# eurofima.net
KiCad netlist of a schematic drawn in EAGLE
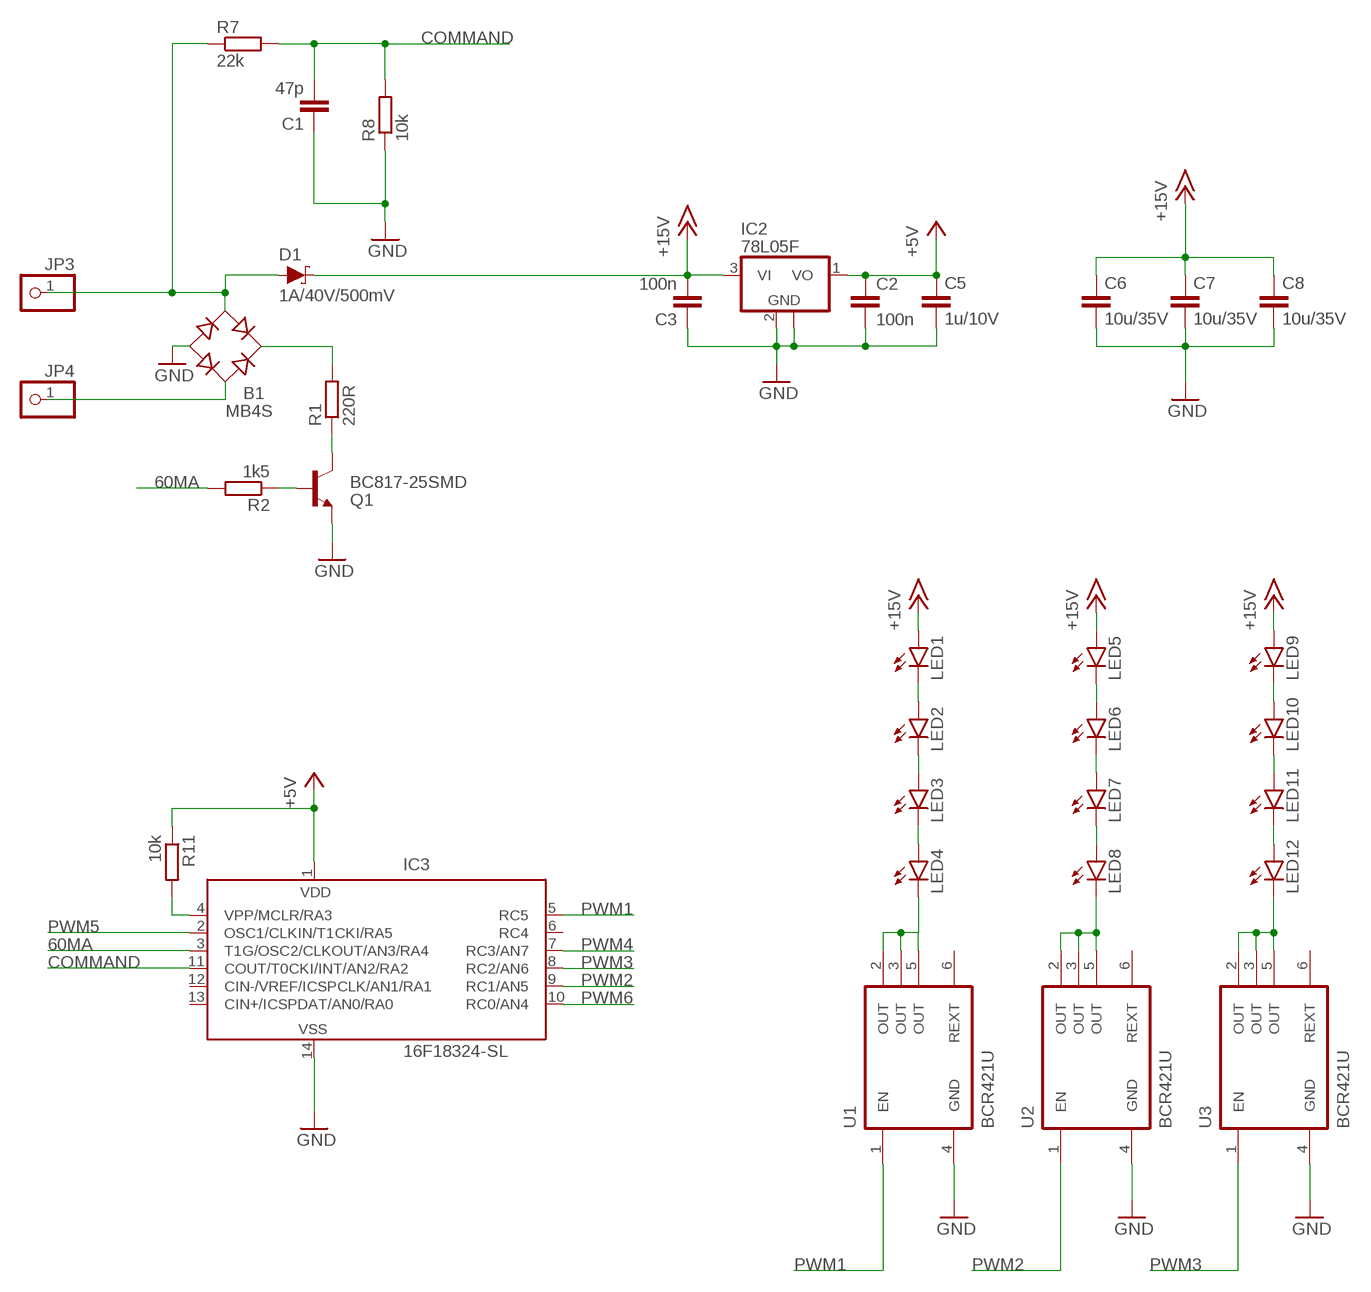
[diagram p0: schematic, sheet 1]

(export (version "E")
  (design (tool "Eeschema 10.0.6"))
  (components
    (comp (ref "B1")
      (value "MB4S")
      (footprint "eagle-import:SOIC-4")
      (libsource (lib "eagle-import") (part "MBS4"))
    )
    (comp (ref "C1")
      (value "47p")
      (footprint "eagle-import:C0805")
      (libsource (lib "eagle-import") (part "C-EUC0805"))
    )
    (comp (ref "C2")
      (value "100n")
      (footprint "eagle-import:C3216")
      (libsource (lib "eagle-import") (part "C-EUC3216"))
    )
    (comp (ref "C3")
      (value "100n")
      (footprint "eagle-import:C3216")
      (libsource (lib "eagle-import") (part "C-EUC3216"))
    )
    (comp (ref "C5")
      (value "1u/10V")
      (footprint "eagle-import:C3216")
      (libsource (lib "eagle-import") (part "C-EUC3216"))
    )
    (comp (ref "C6")
      (value "10u/35V")
      (footprint "eagle-import:C3216")
      (libsource (lib "eagle-import") (part "C-EUC3216"))
    )
    (comp (ref "C7")
      (value "10u/35V")
      (footprint "eagle-import:C3216")
      (libsource (lib "eagle-import") (part "C-EUC3216"))
    )
    (comp (ref "C8")
      (value "10u/35V")
      (footprint "eagle-import:C3216")
      (libsource (lib "eagle-import") (part "C-EUC3216"))
    )
    (comp (ref "D1")
      (value "1A/40V/500mV")
      (footprint "eagle-import:SMA-DIODE")
      (libsource (lib "eagle-import") (part "DIODE-SCHOTTKY-SS14"))
    )
    (comp (ref "IC2")
      (value "78L05F")
      (footprint "eagle-import:SOT89")
      (libsource (lib "eagle-import") (part "78LF05"))
    )
    (comp (ref "IC3")
      (value "16F18324-SL")
      (footprint "eagle-import:SO-14")
      (fields (field (name "MF") "MICROCHIP") (field (name "MPN") "PIC16F676-I/SL"))
      (libsource (lib "eagle-import") (part "PIC16F676SL"))
    )
    (comp (ref "JP3")
      (value "PINHD-1X1")
      (footprint "eagle-import:1X01")
      (libsource (lib "eagle-import") (part "PINHD-1X1"))
    )
    (comp (ref "JP4")
      (value "PINHD-1X1")
      (footprint "eagle-import:1X01")
      (libsource (lib "eagle-import") (part "PINHD-1X1"))
    )
    (comp (ref "LED1")
      (value "LEDKA-3528ASYC")
      (footprint "eagle-import:KA-3528ASYC")
      (libsource (lib "eagle-import") (part "LEDKA-3528ASYC"))
    )
    (comp (ref "LED2")
      (value "LEDKA-3528ASYC")
      (footprint "eagle-import:KA-3528ASYC")
      (libsource (lib "eagle-import") (part "LEDKA-3528ASYC"))
    )
    (comp (ref "LED3")
      (value "LEDKA-3528ASYC")
      (footprint "eagle-import:KA-3528ASYC")
      (libsource (lib "eagle-import") (part "LEDKA-3528ASYC"))
    )
    (comp (ref "LED4")
      (value "LEDKA-3528ASYC")
      (footprint "eagle-import:KA-3528ASYC")
      (libsource (lib "eagle-import") (part "LEDKA-3528ASYC"))
    )
    (comp (ref "LED5")
      (value "LEDKA-3528ASYC")
      (footprint "eagle-import:KA-3528ASYC")
      (libsource (lib "eagle-import") (part "LEDKA-3528ASYC"))
    )
    (comp (ref "LED6")
      (value "LEDKA-3528ASYC")
      (footprint "eagle-import:KA-3528ASYC")
      (libsource (lib "eagle-import") (part "LEDKA-3528ASYC"))
    )
    (comp (ref "LED7")
      (value "LEDKA-3528ASYC")
      (footprint "eagle-import:KA-3528ASYC")
      (libsource (lib "eagle-import") (part "LEDKA-3528ASYC"))
    )
    (comp (ref "LED8")
      (value "LEDKA-3528ASYC")
      (footprint "eagle-import:KA-3528ASYC")
      (libsource (lib "eagle-import") (part "LEDKA-3528ASYC"))
    )
    (comp (ref "LED9")
      (value "LEDKA-3528ASYC")
      (footprint "eagle-import:KA-3528ASYC")
      (libsource (lib "eagle-import") (part "LEDKA-3528ASYC"))
    )
    (comp (ref "LED10")
      (value "LEDKA-3528ASYC")
      (footprint "eagle-import:KA-3528ASYC")
      (libsource (lib "eagle-import") (part "LEDKA-3528ASYC"))
    )
    (comp (ref "LED11")
      (value "LEDKA-3528ASYC")
      (footprint "eagle-import:KA-3528ASYC")
      (libsource (lib "eagle-import") (part "LEDKA-3528ASYC"))
    )
    (comp (ref "LED12")
      (value "LEDKA-3528ASYC")
      (footprint "eagle-import:KA-3528ASYC")
      (libsource (lib "eagle-import") (part "LEDKA-3528ASYC"))
    )
    (comp (ref "Q1")
      (value "BC817-25SMD")
      (footprint "eagle-import:SOT23-BEC")
      (libsource (lib "eagle-import") (part "BC817SMD-25"))
    )
    (comp (ref "R1")
      (value "220R")
      (footprint "eagle-import:R1206")
      (libsource (lib "eagle-import") (part "R-EU_R1206"))
    )
    (comp (ref "R2")
      (value "1k5")
      (footprint "eagle-import:R1206")
      (libsource (lib "eagle-import") (part "R-EU_R1206"))
    )
    (comp (ref "R7")
      (value "22k")
      (footprint "eagle-import:R1206")
      (libsource (lib "eagle-import") (part "R-EU_R1206"))
    )
    (comp (ref "R8")
      (value "10k")
      (footprint "eagle-import:R1206")
      (libsource (lib "eagle-import") (part "R-EU_R1206"))
    )
    (comp (ref "R11")
      (value "10k")
      (footprint "eagle-import:R1206")
      (libsource (lib "eagle-import") (part "R-EU_R1206"))
    )
    (comp (ref "U1")
      (value "BCR421U")
      (footprint "eagle-import:SC74-6")
      (fields (field (name "MF") "Infineon"))
      (libsource (lib "eagle-import") (part "BCR421U"))
    )
    (comp (ref "U2")
      (value "BCR421U")
      (footprint "eagle-import:SC74-6")
      (fields (field (name "MF") "Infineon"))
      (libsource (lib "eagle-import") (part "BCR421U"))
    )
    (comp (ref "U3")
      (value "BCR421U")
      (footprint "eagle-import:SC74-6")
      (fields (field (name "MF") "Infineon"))
      (libsource (lib "eagle-import") (part "BCR421U"))
    )
  )
  (nets
    (net (code "1") (name "+5V") (class "Default")
      (node (ref "C2") (pin "1") (pinfunction "1_1") (pintype "passive"))
      (node (ref "C5") (pin "1") (pinfunction "1_1") (pintype "passive"))
      (node (ref "IC2") (pin "1") (pinfunction "VO_1") (pintype "passive"))
      (node (ref "IC3") (pin "1") (pinfunction "VDD_1") (pintype "power_in"))
      (node (ref "R11") (pin "1") (pinfunction "1_1") (pintype "passive"))
    )
    (net (code "2") (name "+15V") (class "Default")
      (node (ref "C3") (pin "2") (pinfunction "2_2") (pintype "passive"))
      (node (ref "C6") (pin "1") (pinfunction "1_1") (pintype "passive"))
      (node (ref "C7") (pin "1") (pinfunction "1_1") (pintype "passive"))
      (node (ref "C8") (pin "1") (pinfunction "1_1") (pintype "passive"))
      (node (ref "D1") (pin "C") (pinfunction "C_C") (pintype "passive"))
      (node (ref "IC2") (pin "3") (pinfunction "VI_3") (pintype "input"))
      (node (ref "LED1") (pin "A") (pinfunction "A_A") (pintype "passive"))
      (node (ref "LED5") (pin "A") (pinfunction "A_A") (pintype "passive"))
      (node (ref "LED9") (pin "A") (pinfunction "A_A") (pintype "passive"))
    )
    (net (code "3") (name "/60MA") (class "Default")
      (node (ref "IC3") (pin "3") (pinfunction "T1G/OSC2/CLKOUT/AN3/RA4_3") (pintype "bidirectional"))
      (node (ref "R2") (pin "2") (pinfunction "2_2") (pintype "passive"))
    )
    (net (code "4") (name "/COMMAND") (class "Default")
      (node (ref "C1") (pin "2") (pinfunction "2_2") (pintype "passive"))
      (node (ref "IC3") (pin "11") (pinfunction "COUT/T0CKI/INT/AN2/RA2_11") (pintype "bidirectional"))
      (node (ref "R7") (pin "2") (pinfunction "2_2") (pintype "passive"))
      (node (ref "R8") (pin "2") (pinfunction "2_2") (pintype "passive"))
    )
    (net (code "5") (name "/PWM1") (class "Default")
      (node (ref "IC3") (pin "5") (pinfunction "RC5_5") (pintype "bidirectional"))
      (node (ref "U1") (pin "1") (pinfunction "EN_1") (pintype "input"))
    )
    (net (code "6") (name "/PWM2") (class "Default")
      (node (ref "IC3") (pin "9") (pinfunction "RC1/AN5_9") (pintype "bidirectional"))
      (node (ref "U2") (pin "1") (pinfunction "EN_1") (pintype "input"))
    )
    (net (code "7") (name "/PWM3") (class "Default")
      (node (ref "IC3") (pin "8") (pinfunction "RC2/AN6_8") (pintype "bidirectional"))
      (node (ref "U3") (pin "1") (pinfunction "EN_1") (pintype "input"))
    )
    (net (code "8") (name "/PWM4") (class "Default")
      (node (ref "IC3") (pin "7") (pinfunction "RC3/AN7_7") (pintype "bidirectional"))
    )
    (net (code "9") (name "/PWM5") (class "Default")
      (node (ref "IC3") (pin "2") (pinfunction "OSC1/CLKIN/T1CKI/RA5_2") (pintype "bidirectional"))
    )
    (net (code "10") (name "/PWM6") (class "Default")
      (node (ref "IC3") (pin "10") (pinfunction "RC0/AN4_10") (pintype "bidirectional"))
    )
    (net (code "11") (name "GND") (class "Default")
      (node (ref "B1") (pin "-") (pinfunction "-_-") (pintype "passive"))
      (node (ref "C1") (pin "1") (pinfunction "1_1") (pintype "passive"))
      (node (ref "C2") (pin "2") (pinfunction "2_2") (pintype "passive"))
      (node (ref "C3") (pin "1") (pinfunction "1_1") (pintype "passive"))
      (node (ref "C5") (pin "2") (pinfunction "2_2") (pintype "passive"))
      (node (ref "C6") (pin "2") (pinfunction "2_2") (pintype "passive"))
      (node (ref "C7") (pin "2") (pinfunction "2_2") (pintype "passive"))
      (node (ref "C8") (pin "2") (pinfunction "2_2") (pintype "passive"))
      (node (ref "IC2") (pin "2") (pinfunction "GND_2") (pintype "passive"))
      (node (ref "IC2") (pin "2@1") (pinfunction "GND_2@1") (pintype "passive"))
      (node (ref "IC3") (pin "14") (pinfunction "VSS_14") (pintype "power_in"))
      (node (ref "Q1") (pin "E") (pinfunction "E_E") (pintype "passive"))
      (node (ref "R8") (pin "1") (pinfunction "1_1") (pintype "passive"))
      (node (ref "U1") (pin "4") (pinfunction "GND_4") (pintype "input"))
      (node (ref "U2") (pin "4") (pinfunction "GND_4") (pintype "input"))
      (node (ref "U3") (pin "4") (pinfunction "GND_4") (pintype "input"))
    )
    (net (code "12") (name "Net-(B1-AC1)") (class "Default")
      (node (ref "B1") (pin "~1") (pinfunction "AC1_~1") (pintype "passive"))
      (node (ref "D1") (pin "A") (pinfunction "A_A") (pintype "passive"))
      (node (ref "JP3") (pin "1") (pinfunction "1_1") (pintype "passive"))
      (node (ref "R7") (pin "1") (pinfunction "1_1") (pintype "passive"))
    )
    (net (code "13") (name "Net-(B1-AC2)") (class "Default")
      (node (ref "B1") (pin "~2") (pinfunction "AC2_~2") (pintype "passive"))
      (node (ref "JP4") (pin "1") (pinfunction "1_1") (pintype "passive"))
    )
    (net (code "14") (name "Net-(B1-Pad+)") (class "Default")
      (node (ref "B1") (pin "+") (pinfunction "+_+") (pintype "passive"))
      (node (ref "R1") (pin "2") (pinfunction "2_2") (pintype "passive"))
    )
    (net (code "15") (name "Net-(IC3-VPP{slash}MCLR{slash}RA3)") (class "Default")
      (node (ref "IC3") (pin "4") (pinfunction "VPP/MCLR/RA3_4") (pintype "input"))
      (node (ref "R11") (pin "2") (pinfunction "2_2") (pintype "passive"))
    )
    (net (code "16") (name "Net-(LED1-PadC)") (class "Default")
      (node (ref "LED1") (pin "C") (pinfunction "C_C") (pintype "passive"))
      (node (ref "LED2") (pin "A") (pinfunction "A_A") (pintype "passive"))
    )
    (net (code "17") (name "Net-(LED2-PadC)") (class "Default")
      (node (ref "LED2") (pin "C") (pinfunction "C_C") (pintype "passive"))
      (node (ref "LED3") (pin "A") (pinfunction "A_A") (pintype "passive"))
    )
    (net (code "18") (name "Net-(LED3-PadC)") (class "Default")
      (node (ref "LED3") (pin "C") (pinfunction "C_C") (pintype "passive"))
      (node (ref "LED4") (pin "A") (pinfunction "A_A") (pintype "passive"))
    )
    (net (code "19") (name "Net-(LED4-PadC)") (class "Default")
      (node (ref "LED4") (pin "C") (pinfunction "C_C") (pintype "passive"))
      (node (ref "U1") (pin "2") (pinfunction "OUT_2") (pintype "open_collector"))
      (node (ref "U1") (pin "3") (pinfunction "OUT_3") (pintype "open_collector"))
      (node (ref "U1") (pin "5") (pinfunction "OUT_5") (pintype "open_collector"))
    )
    (net (code "20") (name "Net-(LED5-PadC)") (class "Default")
      (node (ref "LED5") (pin "C") (pinfunction "C_C") (pintype "passive"))
      (node (ref "LED6") (pin "A") (pinfunction "A_A") (pintype "passive"))
    )
    (net (code "21") (name "Net-(LED6-PadC)") (class "Default")
      (node (ref "LED6") (pin "C") (pinfunction "C_C") (pintype "passive"))
      (node (ref "LED7") (pin "A") (pinfunction "A_A") (pintype "passive"))
    )
    (net (code "22") (name "Net-(LED7-PadC)") (class "Default")
      (node (ref "LED7") (pin "C") (pinfunction "C_C") (pintype "passive"))
      (node (ref "LED8") (pin "A") (pinfunction "A_A") (pintype "passive"))
    )
    (net (code "23") (name "Net-(LED8-PadC)") (class "Default")
      (node (ref "LED8") (pin "C") (pinfunction "C_C") (pintype "passive"))
      (node (ref "U2") (pin "2") (pinfunction "OUT_2") (pintype "open_collector"))
      (node (ref "U2") (pin "3") (pinfunction "OUT_3") (pintype "open_collector"))
      (node (ref "U2") (pin "5") (pinfunction "OUT_5") (pintype "open_collector"))
    )
    (net (code "24") (name "Net-(LED10-PadA)") (class "Default")
      (node (ref "LED10") (pin "A") (pinfunction "A_A") (pintype "passive"))
      (node (ref "LED9") (pin "C") (pinfunction "C_C") (pintype "passive"))
    )
    (net (code "25") (name "Net-(LED10-PadC)") (class "Default")
      (node (ref "LED10") (pin "C") (pinfunction "C_C") (pintype "passive"))
      (node (ref "LED11") (pin "A") (pinfunction "A_A") (pintype "passive"))
    )
    (net (code "26") (name "Net-(LED11-PadC)") (class "Default")
      (node (ref "LED11") (pin "C") (pinfunction "C_C") (pintype "passive"))
      (node (ref "LED12") (pin "A") (pinfunction "A_A") (pintype "passive"))
    )
    (net (code "27") (name "Net-(LED12-PadC)") (class "Default")
      (node (ref "LED12") (pin "C") (pinfunction "C_C") (pintype "passive"))
      (node (ref "U3") (pin "2") (pinfunction "OUT_2") (pintype "open_collector"))
      (node (ref "U3") (pin "3") (pinfunction "OUT_3") (pintype "open_collector"))
      (node (ref "U3") (pin "5") (pinfunction "OUT_5") (pintype "open_collector"))
    )
    (net (code "28") (name "Net-(Q1-PadB)") (class "Default")
      (node (ref "Q1") (pin "B") (pinfunction "B_B") (pintype "passive"))
      (node (ref "R2") (pin "1") (pinfunction "1_1") (pintype "passive"))
    )
    (net (code "29") (name "Net-(Q1-PadC)") (class "Default")
      (node (ref "Q1") (pin "C") (pinfunction "C_C") (pintype "passive"))
      (node (ref "R1") (pin "1") (pinfunction "1_1") (pintype "passive"))
    )
    (net (code "30") (name "unconnected-(IC3-CIN+{slash}ICSPDAT{slash}AN0{slash}RA0-Pad13)") (class "Default")
      (node (ref "IC3") (pin "13") (pinfunction "CIN+/ICSPDAT/AN0/RA0_13") (pintype "bidirectional"))
    )
    (net (code "31") (name "unconnected-(IC3-CIN-{slash}VREF{slash}ICSPCLK{slash}AN1{slash}RA1-Pad12)") (class "Default")
      (node (ref "IC3") (pin "12") (pinfunction "CIN-/VREF/ICSPCLK/AN1/RA1_12") (pintype "bidirectional"))
    )
    (net (code "32") (name "unconnected-(IC3-RC4-Pad6)") (class "Default")
      (node (ref "IC3") (pin "6") (pinfunction "RC4_6") (pintype "bidirectional"))
    )
    (net (code "33") (name "unconnected-(U1-REXT-Pad6)") (class "Default")
      (node (ref "U1") (pin "6") (pinfunction "REXT_6") (pintype "bidirectional"))
    )
    (net (code "34") (name "unconnected-(U2-REXT-Pad6)") (class "Default")
      (node (ref "U2") (pin "6") (pinfunction "REXT_6") (pintype "bidirectional"))
    )
    (net (code "35") (name "unconnected-(U3-REXT-Pad6)") (class "Default")
      (node (ref "U3") (pin "6") (pinfunction "REXT_6") (pintype "bidirectional"))
    )
  )
)
